# SLOW.net
KiCad netlist of a schematic drawn in Altium Designer
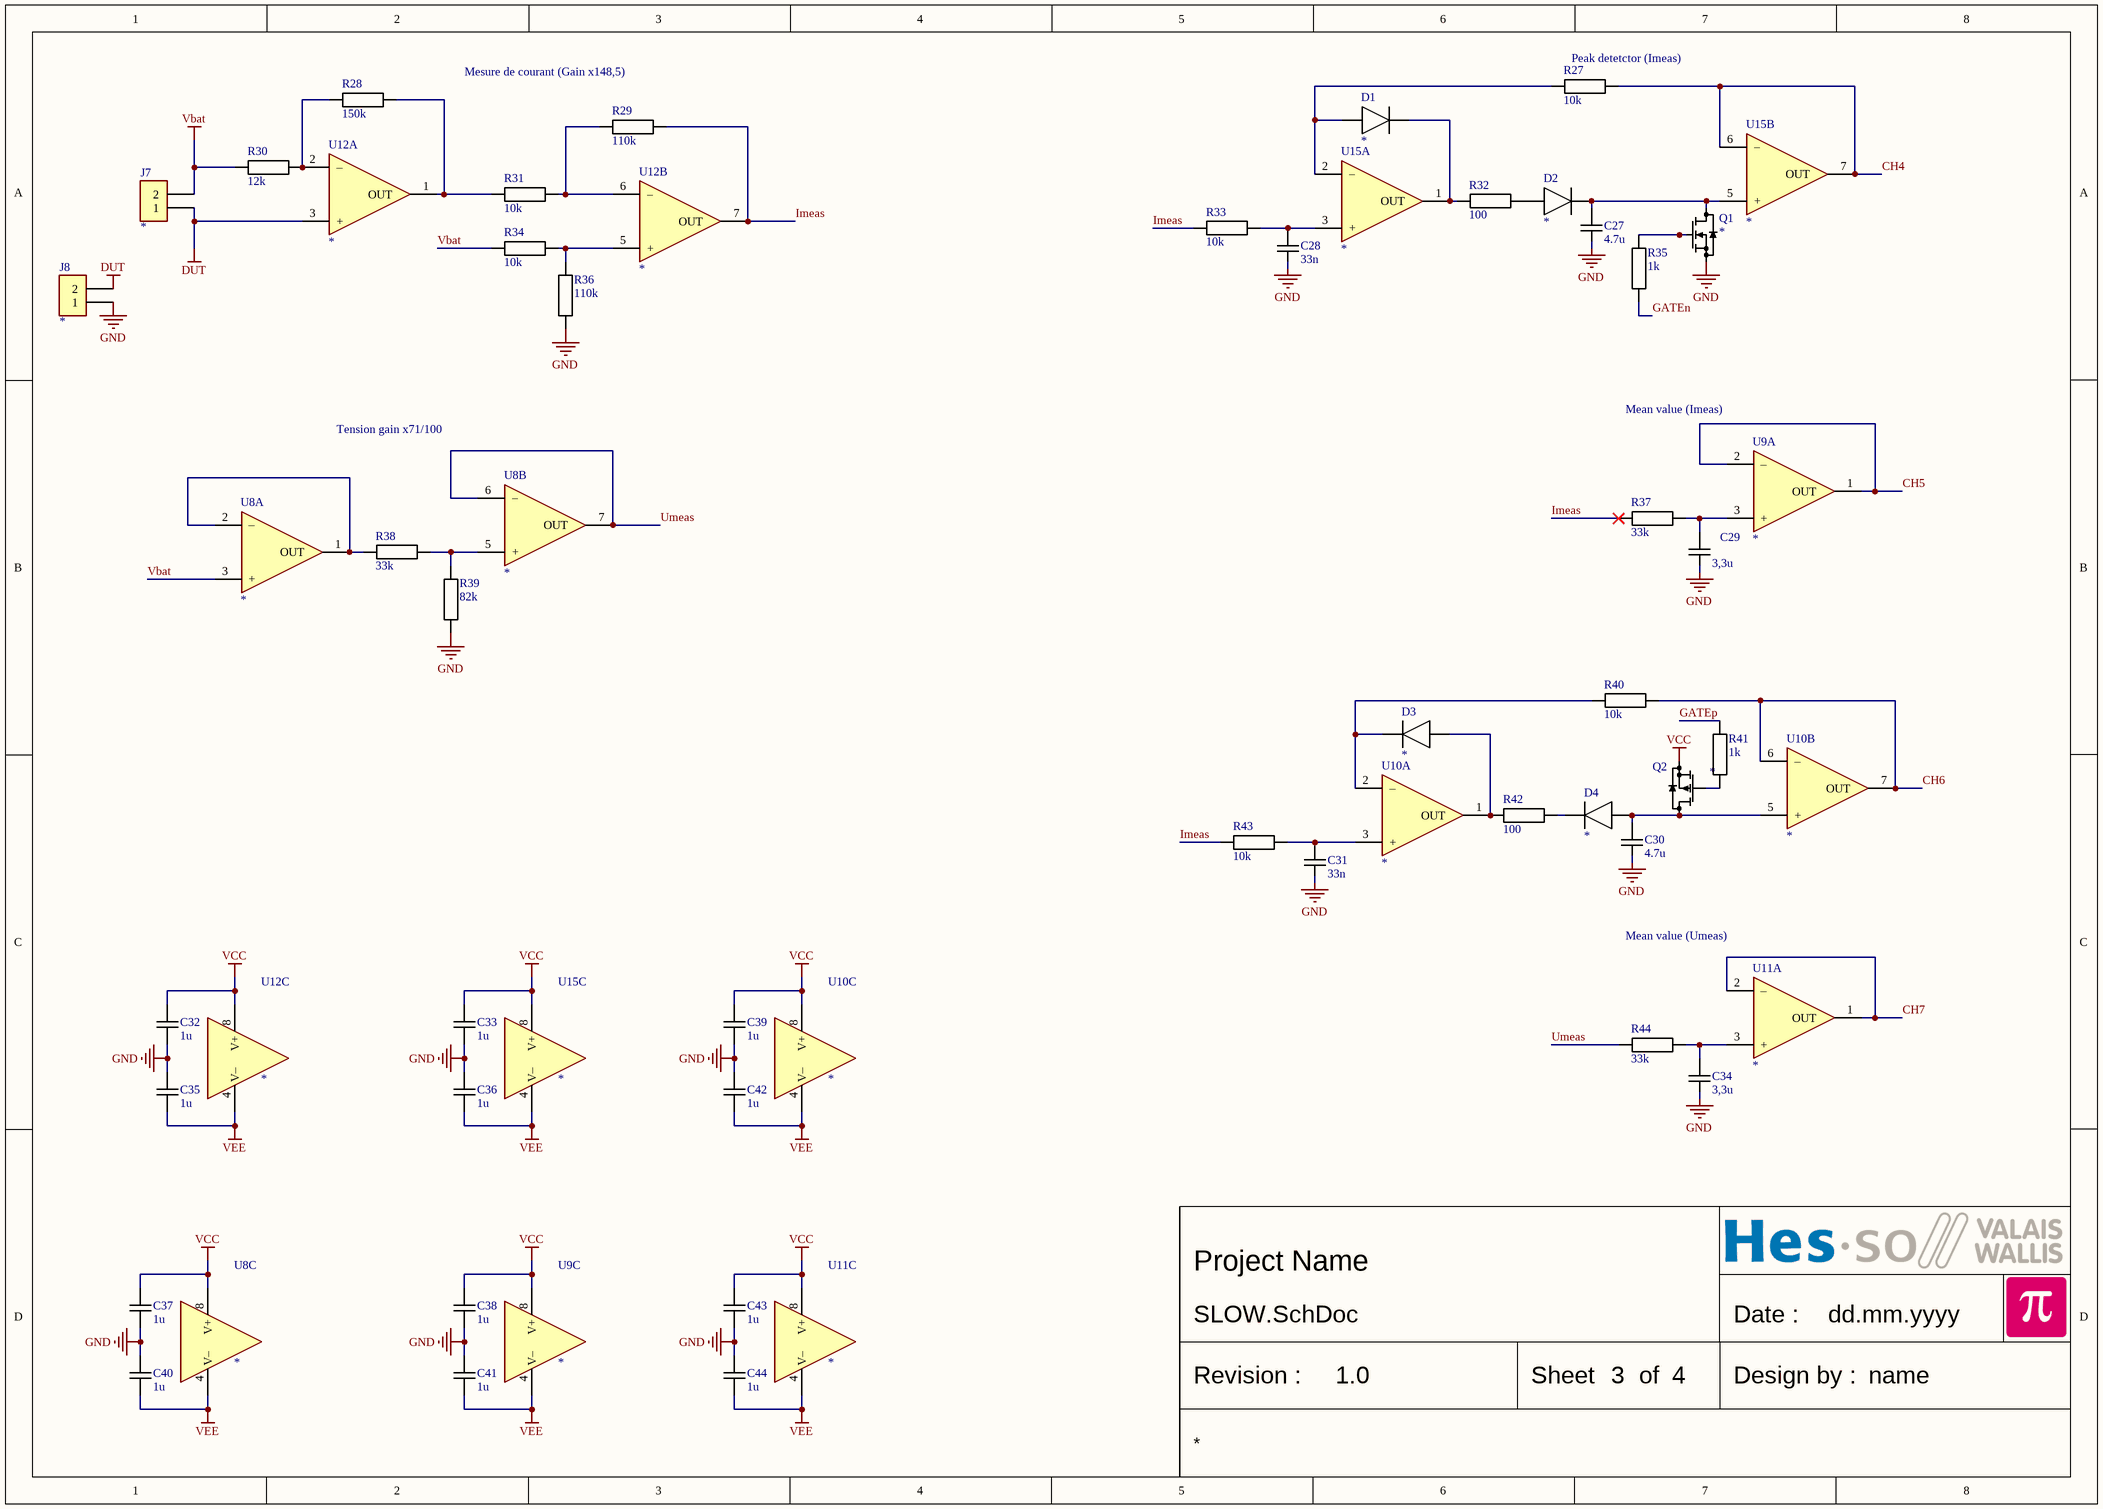
[diagram p0: SLOW.SchDoc]

(export (version "E")
  (design (tool "Eeschema 10.0.6"))
  (components
    (comp (ref "C27")
      (value "4.7u")
      (footprint "CAPACITOR 1005 REFLOW")
      (description "Capacitor")
      (libsource (lib "Capacitor") (part "Capacitor"))
    )
    (comp (ref "C28")
      (value "33n")
      (footprint "CAPACITOR 1005 REFLOW")
      (description "Capacitor")
      (libsource (lib "Capacitor") (part "Capacitor"))
    )
    (comp (ref "C29")
      (value "3,3u")
      (footprint "CAPACITOR 1005 REFLOW")
      (description "Capacitor")
      (libsource (lib "Capacitor") (part "Capacitor"))
    )
    (comp (ref "C30")
      (value "4.7u")
      (footprint "CAPACITOR 1005 REFLOW")
      (description "Capacitor")
      (libsource (lib "Capacitor") (part "Capacitor"))
    )
    (comp (ref "C31")
      (value "33n")
      (footprint "CAPACITOR 1005 REFLOW")
      (description "Capacitor")
      (libsource (lib "Capacitor") (part "Capacitor"))
    )
    (comp (ref "C32")
      (value "1u")
      (footprint "CAPACITOR 1005 REFLOW")
      (description "Capacitor")
      (libsource (lib "Capacitor") (part "Capacitor"))
    )
    (comp (ref "C33")
      (value "1u")
      (footprint "CAPACITOR 1005 REFLOW")
      (description "Capacitor")
      (libsource (lib "Capacitor") (part "Capacitor"))
    )
    (comp (ref "C34")
      (value "3,3u")
      (footprint "CAPACITOR 1005 REFLOW")
      (description "Capacitor")
      (libsource (lib "Capacitor") (part "Capacitor"))
    )
    (comp (ref "C35")
      (value "1u")
      (footprint "CAPACITOR 1005 REFLOW")
      (description "Capacitor")
      (libsource (lib "Capacitor") (part "Capacitor"))
    )
    (comp (ref "C36")
      (value "1u")
      (footprint "CAPACITOR 1005 REFLOW")
      (description "Capacitor")
      (libsource (lib "Capacitor") (part "Capacitor"))
    )
    (comp (ref "C37")
      (value "1u")
      (footprint "CAPACITOR 1005 REFLOW")
      (description "Capacitor")
      (libsource (lib "Capacitor") (part "Capacitor"))
    )
    (comp (ref "C38")
      (value "1u")
      (footprint "CAPACITOR 1005 REFLOW")
      (description "Capacitor")
      (libsource (lib "Capacitor") (part "Capacitor"))
    )
    (comp (ref "C39")
      (value "1u")
      (footprint "CAPACITOR 1005 REFLOW")
      (description "Capacitor")
      (libsource (lib "Capacitor") (part "Capacitor"))
    )
    (comp (ref "C40")
      (value "1u")
      (footprint "CAPACITOR 1005 REFLOW")
      (description "Capacitor")
      (libsource (lib "Capacitor") (part "Capacitor"))
    )
    (comp (ref "C41")
      (value "1u")
      (footprint "CAPACITOR 1005 REFLOW")
      (description "Capacitor")
      (libsource (lib "Capacitor") (part "Capacitor"))
    )
    (comp (ref "C42")
      (value "1u")
      (footprint "CAPACITOR 1005 REFLOW")
      (description "Capacitor")
      (libsource (lib "Capacitor") (part "Capacitor"))
    )
    (comp (ref "C43")
      (value "1u")
      (footprint "CAPACITOR 1005 REFLOW")
      (description "Capacitor")
      (libsource (lib "Capacitor") (part "Capacitor"))
    )
    (comp (ref "C44")
      (value "1u")
      (footprint "CAPACITOR 1005 REFLOW")
      (description "Capacitor")
      (libsource (lib "Capacitor") (part "Capacitor"))
    )
    (comp (ref "D1")
      (value "*")
      (footprint "DIODE SOD323 REFLOW")
      (description "Diode generic 2 leads")
      (libsource (lib "Diode") (part "DIODE"))
    )
    (comp (ref "D2")
      (value "*")
      (footprint "DIODE SOD323 REFLOW")
      (description "Diode generic 2 leads")
      (libsource (lib "Diode") (part "DIODE"))
    )
    (comp (ref "D3")
      (value "*")
      (footprint "DIODE SOD323 REFLOW")
      (description "Diode generic 2 leads")
      (libsource (lib "Diode") (part "DIODE"))
    )
    (comp (ref "D4")
      (value "*")
      (footprint "DIODE SOD323 REFLOW")
      (description "Diode generic 2 leads")
      (libsource (lib "Diode") (part "DIODE"))
    )
    (comp (ref "J7")
      (value "*")
      (footprint "WE 691312510002")
      (description "PCB terminal block")
      (libsource (lib "Header") (part "Header2"))
    )
    (comp (ref "J8")
      (value "*")
      (footprint "WE 691312510002")
      (description "PCB terminal block")
      (libsource (lib "Header") (part "Header2"))
    )
    (comp (ref "Q1")
      (value "*")
      (footprint "SOT23 P0.95 C1.6x3.0 H1.3")
      (description "Generic MOS-N")
      (libsource (lib "Transistor") (part "MOS-N SOT23 S-D-G"))
    )
    (comp (ref "Q2")
      (value "*")
      (footprint "SOT23 P0.95 C1.6x3.0 H1.3")
      (description "Generic MOS-P")
      (libsource (lib "Transistor") (part "MOS-P SOT23 G-S-D"))
    )
    (comp (ref "R27")
      (value "10k")
      (footprint "RESISTOR 1005 REFLOW")
      (description "Resistor")
      (libsource (lib "Resistor") (part "Resistor"))
    )
    (comp (ref "R28")
      (value "150k")
      (footprint "RESISTOR 1005 REFLOW")
      (description "Resistor")
      (libsource (lib "Resistor") (part "Resistor"))
    )
    (comp (ref "R29")
      (value "110k")
      (footprint "RESISTOR 1005 REFLOW")
      (description "Resistor")
      (libsource (lib "Resistor") (part "Resistor"))
    )
    (comp (ref "R30")
      (value "12k")
      (footprint "RESISTOR 1005 REFLOW")
      (description "Resistor")
      (libsource (lib "Resistor") (part "Resistor"))
    )
    (comp (ref "R31")
      (value "10k")
      (footprint "RESISTOR 1005 REFLOW")
      (description "Resistor")
      (libsource (lib "Resistor") (part "Resistor"))
    )
    (comp (ref "R32")
      (value "100")
      (footprint "RESISTOR 1005 REFLOW")
      (description "Resistor")
      (libsource (lib "Resistor") (part "Resistor"))
    )
    (comp (ref "R33")
      (value "10k")
      (footprint "RESISTOR 1005 REFLOW")
      (description "Resistor")
      (libsource (lib "Resistor") (part "Resistor"))
    )
    (comp (ref "R34")
      (value "10k")
      (footprint "RESISTOR 1005 REFLOW")
      (description "Resistor")
      (libsource (lib "Resistor") (part "Resistor"))
    )
    (comp (ref "R35")
      (value "1k")
      (footprint "RESISTOR 1005 REFLOW")
      (description "Resistor")
      (libsource (lib "Resistor") (part "Resistor"))
    )
    (comp (ref "R36")
      (value "110k")
      (footprint "RESISTOR 1005 REFLOW")
      (description "Resistor")
      (libsource (lib "Resistor") (part "Resistor"))
    )
    (comp (ref "R37")
      (value "33k")
      (footprint "RESISTOR 1005 REFLOW")
      (description "Resistor")
      (libsource (lib "Resistor") (part "Resistor"))
    )
    (comp (ref "R38")
      (value "33k")
      (footprint "RESISTOR 1005 REFLOW")
      (description "Resistor")
      (libsource (lib "Resistor") (part "Resistor"))
    )
    (comp (ref "R39")
      (value "82k")
      (footprint "RESISTOR 1005 REFLOW")
      (description "Resistor")
      (libsource (lib "Resistor") (part "Resistor"))
    )
    (comp (ref "R40")
      (value "10k")
      (footprint "RESISTOR 1005 REFLOW")
      (description "Resistor")
      (libsource (lib "Resistor") (part "Resistor"))
    )
    (comp (ref "R41")
      (value "1k")
      (footprint "RESISTOR 1005 REFLOW")
      (description "Resistor")
      (libsource (lib "Resistor") (part "Resistor"))
    )
    (comp (ref "R42")
      (value "100")
      (footprint "RESISTOR 1005 REFLOW")
      (description "Resistor")
      (libsource (lib "Resistor") (part "Resistor"))
    )
    (comp (ref "R43")
      (value "10k")
      (footprint "RESISTOR 1005 REFLOW")
      (description "Resistor")
      (libsource (lib "Resistor") (part "Resistor"))
    )
    (comp (ref "R44")
      (value "33k")
      (footprint "RESISTOR 1005 REFLOW")
      (description "Resistor")
      (libsource (lib "Resistor") (part "Resistor"))
    )
    (comp (ref "U8")
      (value "*")
      (footprint "SO8 P1.27 C4.0X5.0 H1.75")
      (description "Generic dual OPA 8 pins")
      (libsource (lib "Amplifier") (part "OPA DUAL"))
    )
    (comp (ref "U9")
      (value "*")
      (footprint "SO8 P1.27 C4.0X5.0 H1.75")
      (description "Generic dual OPA 8 pins")
      (libsource (lib "Amplifier") (part "OPA DUAL"))
    )
    (comp (ref "U10")
      (value "*")
      (footprint "SO8 P1.27 C4.0X5.0 H1.75")
      (description "Generic dual OPA 8 pins")
      (libsource (lib "Amplifier") (part "OPA DUAL"))
    )
    (comp (ref "U11")
      (value "*")
      (footprint "SO8 P1.27 C4.0X5.0 H1.75")
      (description "Generic dual OPA 8 pins")
      (libsource (lib "Amplifier") (part "OPA DUAL"))
    )
    (comp (ref "U12")
      (value "*")
      (footprint "SO8 P1.27 C4.0X5.0 H1.75")
      (description "Generic dual OPA 8 pins")
      (libsource (lib "Amplifier") (part "OPA DUAL"))
    )
    (comp (ref "U15")
      (value "*")
      (footprint "SO8 P1.27 C4.0X5.0 H1.75")
      (description "Generic dual OPA 8 pins")
      (libsource (lib "Amplifier") (part "OPA DUAL"))
    )
  )
  (nets
    (net (code "1") (name "/CH4") (class "Default")
      (node (ref "R27") (pin "1") (pinfunction "1_1") (pintype "passive"))
      (node (ref "U15") (pin "6") (pinfunction "–_6") (pintype "passive"))
      (node (ref "U15") (pin "7") (pinfunction "OUT_7") (pintype "passive"))
    )
    (net (code "2") (name "/CH5") (class "Default")
      (node (ref "U9") (pin "1") (pinfunction "OUT_1") (pintype "passive"))
      (node (ref "U9") (pin "2") (pinfunction "–_2") (pintype "passive"))
    )
    (net (code "3") (name "/CH6") (class "Default")
      (node (ref "R40") (pin "1") (pinfunction "1_1") (pintype "passive"))
      (node (ref "U10") (pin "6") (pinfunction "–_6") (pintype "passive"))
      (node (ref "U10") (pin "7") (pinfunction "OUT_7") (pintype "passive"))
    )
    (net (code "4") (name "/CH7") (class "Default")
      (node (ref "U11") (pin "1") (pinfunction "OUT_1") (pintype "passive"))
      (node (ref "U11") (pin "2") (pinfunction "–_2") (pintype "passive"))
    )
    (net (code "5") (name "/GATEn") (class "Default")
      (node (ref "R35") (pin "2") (pinfunction "2_2") (pintype "passive"))
    )
    (net (code "6") (name "/GATEp") (class "Default")
      (node (ref "R41") (pin "1") (pinfunction "1_1") (pintype "passive"))
    )
    (net (code "7") (name "/Imeas") (class "Default")
      (node (ref "R29") (pin "2") (pinfunction "2_2") (pintype "passive"))
      (node (ref "R33") (pin "2") (pinfunction "2_2") (pintype "passive"))
      (node (ref "R37") (pin "2") (pinfunction "2_2") (pintype "passive"))
      (node (ref "R43") (pin "2") (pinfunction "2_2") (pintype "passive"))
      (node (ref "U12") (pin "7") (pinfunction "OUT_7") (pintype "passive"))
    )
    (net (code "8") (name "/Umeas") (class "Default")
      (node (ref "R44") (pin "2") (pinfunction "2_2") (pintype "passive"))
      (node (ref "U8") (pin "6") (pinfunction "–_6") (pintype "passive"))
      (node (ref "U8") (pin "7") (pinfunction "OUT_7") (pintype "passive"))
    )
    (net (code "9") (name "DUT") (class "Default")
      (node (ref "J7") (pin "1") (pinfunction "1_1") (pintype "passive"))
      (node (ref "J8") (pin "2") (pinfunction "2_2") (pintype "passive"))
      (node (ref "U12") (pin "3") (pinfunction "+_3") (pintype "passive"))
    )
    (net (code "10") (name "GND") (class "Default")
      (node (ref "C27") (pin "2") (pinfunction "2_2") (pintype "passive"))
      (node (ref "C28") (pin "2") (pinfunction "2_2") (pintype "passive"))
      (node (ref "C29") (pin "2") (pinfunction "2_2") (pintype "passive"))
      (node (ref "C30") (pin "2") (pinfunction "2_2") (pintype "passive"))
      (node (ref "C31") (pin "2") (pinfunction "2_2") (pintype "passive"))
      (node (ref "C32") (pin "2") (pinfunction "2_2") (pintype "passive"))
      (node (ref "C33") (pin "2") (pinfunction "2_2") (pintype "passive"))
      (node (ref "C34") (pin "2") (pinfunction "2_2") (pintype "passive"))
      (node (ref "C35") (pin "1") (pinfunction "1_1") (pintype "passive"))
      (node (ref "C36") (pin "1") (pinfunction "1_1") (pintype "passive"))
      (node (ref "C37") (pin "2") (pinfunction "2_2") (pintype "passive"))
      (node (ref "C38") (pin "2") (pinfunction "2_2") (pintype "passive"))
      (node (ref "C39") (pin "2") (pinfunction "2_2") (pintype "passive"))
      (node (ref "C40") (pin "1") (pinfunction "1_1") (pintype "passive"))
      (node (ref "C41") (pin "1") (pinfunction "1_1") (pintype "passive"))
      (node (ref "C42") (pin "1") (pinfunction "1_1") (pintype "passive"))
      (node (ref "C43") (pin "2") (pinfunction "2_2") (pintype "passive"))
      (node (ref "C44") (pin "1") (pinfunction "1_1") (pintype "passive"))
      (node (ref "J8") (pin "1") (pinfunction "1_1") (pintype "passive"))
      (node (ref "Q1") (pin "2") (pinfunction "S_2") (pintype "passive"))
      (node (ref "R36") (pin "1") (pinfunction "1_1") (pintype "passive"))
      (node (ref "R39") (pin "1") (pinfunction "1_1") (pintype "passive"))
    )
    (net (code "11") (name "Net-(D1-A)") (class "Default")
      (node (ref "D1") (pin "2") (pinfunction "A_2") (pintype "passive"))
      (node (ref "R27") (pin "2") (pinfunction "2_2") (pintype "passive"))
      (node (ref "U15") (pin "2") (pinfunction "–_2") (pintype "passive"))
    )
    (net (code "12") (name "Net-(D1-C)") (class "Default")
      (node (ref "D1") (pin "1") (pinfunction "C_1") (pintype "passive"))
      (node (ref "R32") (pin "2") (pinfunction "2_2") (pintype "passive"))
      (node (ref "U15") (pin "1") (pinfunction "OUT_1") (pintype "passive"))
    )
    (net (code "13") (name "Net-(D2-A)") (class "Default")
      (node (ref "D2") (pin "2") (pinfunction "A_2") (pintype "passive"))
      (node (ref "R32") (pin "1") (pinfunction "1_1") (pintype "passive"))
    )
    (net (code "14") (name "Net-(D2-C)") (class "Default")
      (node (ref "C27") (pin "1") (pinfunction "1_1") (pintype "passive"))
      (node (ref "D2") (pin "1") (pinfunction "C_1") (pintype "passive"))
      (node (ref "Q1") (pin "3") (pinfunction "D_3") (pintype "passive"))
      (node (ref "U15") (pin "5") (pinfunction "+_5") (pintype "passive"))
    )
    (net (code "15") (name "Net-(D3-A)") (class "Default")
      (node (ref "D3") (pin "2") (pinfunction "A_2") (pintype "passive"))
      (node (ref "R42") (pin "2") (pinfunction "2_2") (pintype "passive"))
      (node (ref "U10") (pin "1") (pinfunction "OUT_1") (pintype "passive"))
    )
    (net (code "16") (name "Net-(D3-C)") (class "Default")
      (node (ref "D3") (pin "1") (pinfunction "C_1") (pintype "passive"))
      (node (ref "R40") (pin "2") (pinfunction "2_2") (pintype "passive"))
      (node (ref "U10") (pin "2") (pinfunction "–_2") (pintype "passive"))
    )
    (net (code "17") (name "Net-(D4-A)") (class "Default")
      (node (ref "C30") (pin "1") (pinfunction "1_1") (pintype "passive"))
      (node (ref "D4") (pin "2") (pinfunction "A_2") (pintype "passive"))
      (node (ref "Q2") (pin "3") (pinfunction "D_3") (pintype "passive"))
      (node (ref "U10") (pin "5") (pinfunction "+_5") (pintype "passive"))
    )
    (net (code "18") (name "Net-(D4-C)") (class "Default")
      (node (ref "D4") (pin "1") (pinfunction "C_1") (pintype "passive"))
      (node (ref "R42") (pin "1") (pinfunction "1_1") (pintype "passive"))
    )
    (net (code "19") (name "Net-(Q1-G)") (class "Default")
      (node (ref "Q1") (pin "1") (pinfunction "G_1") (pintype "passive"))
      (node (ref "R35") (pin "1") (pinfunction "1_1") (pintype "passive"))
    )
    (net (code "20") (name "Net-(Q2-G)") (class "Default")
      (node (ref "Q2") (pin "1") (pinfunction "G_1") (pintype "passive"))
      (node (ref "R41") (pin "2") (pinfunction "2_2") (pintype "passive"))
    )
    (net (code "21") (name "Net-(U8A-OUT)") (class "Default")
      (node (ref "R38") (pin "1") (pinfunction "1_1") (pintype "passive"))
      (node (ref "U8") (pin "1") (pinfunction "OUT_1") (pintype "passive"))
      (node (ref "U8") (pin "2") (pinfunction "–_2") (pintype "passive"))
    )
    (net (code "22") (name "Net-(U8B-+)") (class "Default")
      (node (ref "R38") (pin "2") (pinfunction "2_2") (pintype "passive"))
      (node (ref "R39") (pin "2") (pinfunction "2_2") (pintype "passive"))
      (node (ref "U8") (pin "5") (pinfunction "+_5") (pintype "passive"))
    )
    (net (code "23") (name "Net-(U9A-+)") (class "Default")
      (node (ref "C29") (pin "1") (pinfunction "1_1") (pintype "passive"))
      (node (ref "R37") (pin "1") (pinfunction "1_1") (pintype "passive"))
      (node (ref "U9") (pin "3") (pinfunction "+_3") (pintype "passive"))
    )
    (net (code "24") (name "Net-(U10A-+)") (class "Default")
      (node (ref "C31") (pin "1") (pinfunction "1_1") (pintype "passive"))
      (node (ref "R43") (pin "1") (pinfunction "1_1") (pintype "passive"))
      (node (ref "U10") (pin "3") (pinfunction "+_3") (pintype "passive"))
    )
    (net (code "25") (name "Net-(U11A-+)") (class "Default")
      (node (ref "C34") (pin "1") (pinfunction "1_1") (pintype "passive"))
      (node (ref "R44") (pin "1") (pinfunction "1_1") (pintype "passive"))
      (node (ref "U11") (pin "3") (pinfunction "+_3") (pintype "passive"))
    )
    (net (code "26") (name "Net-(U12A-OUT)") (class "Default")
      (node (ref "R28") (pin "2") (pinfunction "2_2") (pintype "passive"))
      (node (ref "R31") (pin "1") (pinfunction "1_1") (pintype "passive"))
      (node (ref "U12") (pin "1") (pinfunction "OUT_1") (pintype "passive"))
    )
    (net (code "27") (name "Net-(U12A-–)") (class "Default")
      (node (ref "R28") (pin "1") (pinfunction "1_1") (pintype "passive"))
      (node (ref "R30") (pin "2") (pinfunction "2_2") (pintype "passive"))
      (node (ref "U12") (pin "2") (pinfunction "–_2") (pintype "passive"))
    )
    (net (code "28") (name "Net-(U12B-+)") (class "Default")
      (node (ref "R34") (pin "2") (pinfunction "2_2") (pintype "passive"))
      (node (ref "R36") (pin "2") (pinfunction "2_2") (pintype "passive"))
      (node (ref "U12") (pin "5") (pinfunction "+_5") (pintype "passive"))
    )
    (net (code "29") (name "Net-(U12B-–)") (class "Default")
      (node (ref "R29") (pin "1") (pinfunction "1_1") (pintype "passive"))
      (node (ref "R31") (pin "2") (pinfunction "2_2") (pintype "passive"))
      (node (ref "U12") (pin "6") (pinfunction "–_6") (pintype "passive"))
    )
    (net (code "30") (name "Net-(U15A-+)") (class "Default")
      (node (ref "C28") (pin "1") (pinfunction "1_1") (pintype "passive"))
      (node (ref "R33") (pin "1") (pinfunction "1_1") (pintype "passive"))
      (node (ref "U15") (pin "3") (pinfunction "+_3") (pintype "passive"))
    )
    (net (code "31") (name "VCC") (class "Default")
      (node (ref "C32") (pin "1") (pinfunction "1_1") (pintype "passive"))
      (node (ref "C33") (pin "1") (pinfunction "1_1") (pintype "passive"))
      (node (ref "C37") (pin "1") (pinfunction "1_1") (pintype "passive"))
      (node (ref "C38") (pin "1") (pinfunction "1_1") (pintype "passive"))
      (node (ref "C39") (pin "1") (pinfunction "1_1") (pintype "passive"))
      (node (ref "C43") (pin "1") (pinfunction "1_1") (pintype "passive"))
      (node (ref "Q2") (pin "2") (pinfunction "S_2") (pintype "passive"))
      (node (ref "U10") (pin "8") (pinfunction "V+_8") (pintype "passive"))
      (node (ref "U11") (pin "8") (pinfunction "V+_8") (pintype "passive"))
      (node (ref "U12") (pin "8") (pinfunction "V+_8") (pintype "passive"))
      (node (ref "U15") (pin "8") (pinfunction "V+_8") (pintype "passive"))
      (node (ref "U8") (pin "8") (pinfunction "V+_8") (pintype "passive"))
      (node (ref "U9") (pin "8") (pinfunction "V+_8") (pintype "passive"))
    )
    (net (code "32") (name "VEE") (class "Default")
      (node (ref "C35") (pin "2") (pinfunction "2_2") (pintype "passive"))
      (node (ref "C36") (pin "2") (pinfunction "2_2") (pintype "passive"))
      (node (ref "C40") (pin "2") (pinfunction "2_2") (pintype "passive"))
      (node (ref "C41") (pin "2") (pinfunction "2_2") (pintype "passive"))
      (node (ref "C42") (pin "2") (pinfunction "2_2") (pintype "passive"))
      (node (ref "C44") (pin "2") (pinfunction "2_2") (pintype "passive"))
      (node (ref "U10") (pin "4") (pinfunction "V–_4") (pintype "passive"))
      (node (ref "U11") (pin "4") (pinfunction "V–_4") (pintype "passive"))
      (node (ref "U12") (pin "4") (pinfunction "V–_4") (pintype "passive"))
      (node (ref "U15") (pin "4") (pinfunction "V–_4") (pintype "passive"))
      (node (ref "U8") (pin "4") (pinfunction "V–_4") (pintype "passive"))
      (node (ref "U9") (pin "4") (pinfunction "V–_4") (pintype "passive"))
    )
    (net (code "33") (name "Vbat") (class "Default")
      (node (ref "J7") (pin "2") (pinfunction "2_2") (pintype "passive"))
      (node (ref "R30") (pin "1") (pinfunction "1_1") (pintype "passive"))
      (node (ref "R34") (pin "1") (pinfunction "1_1") (pintype "passive"))
      (node (ref "U8") (pin "3") (pinfunction "+_3") (pintype "passive"))
    )
  )
)
